# rx.net
KiCad netlist of a schematic drawn in EAGLE
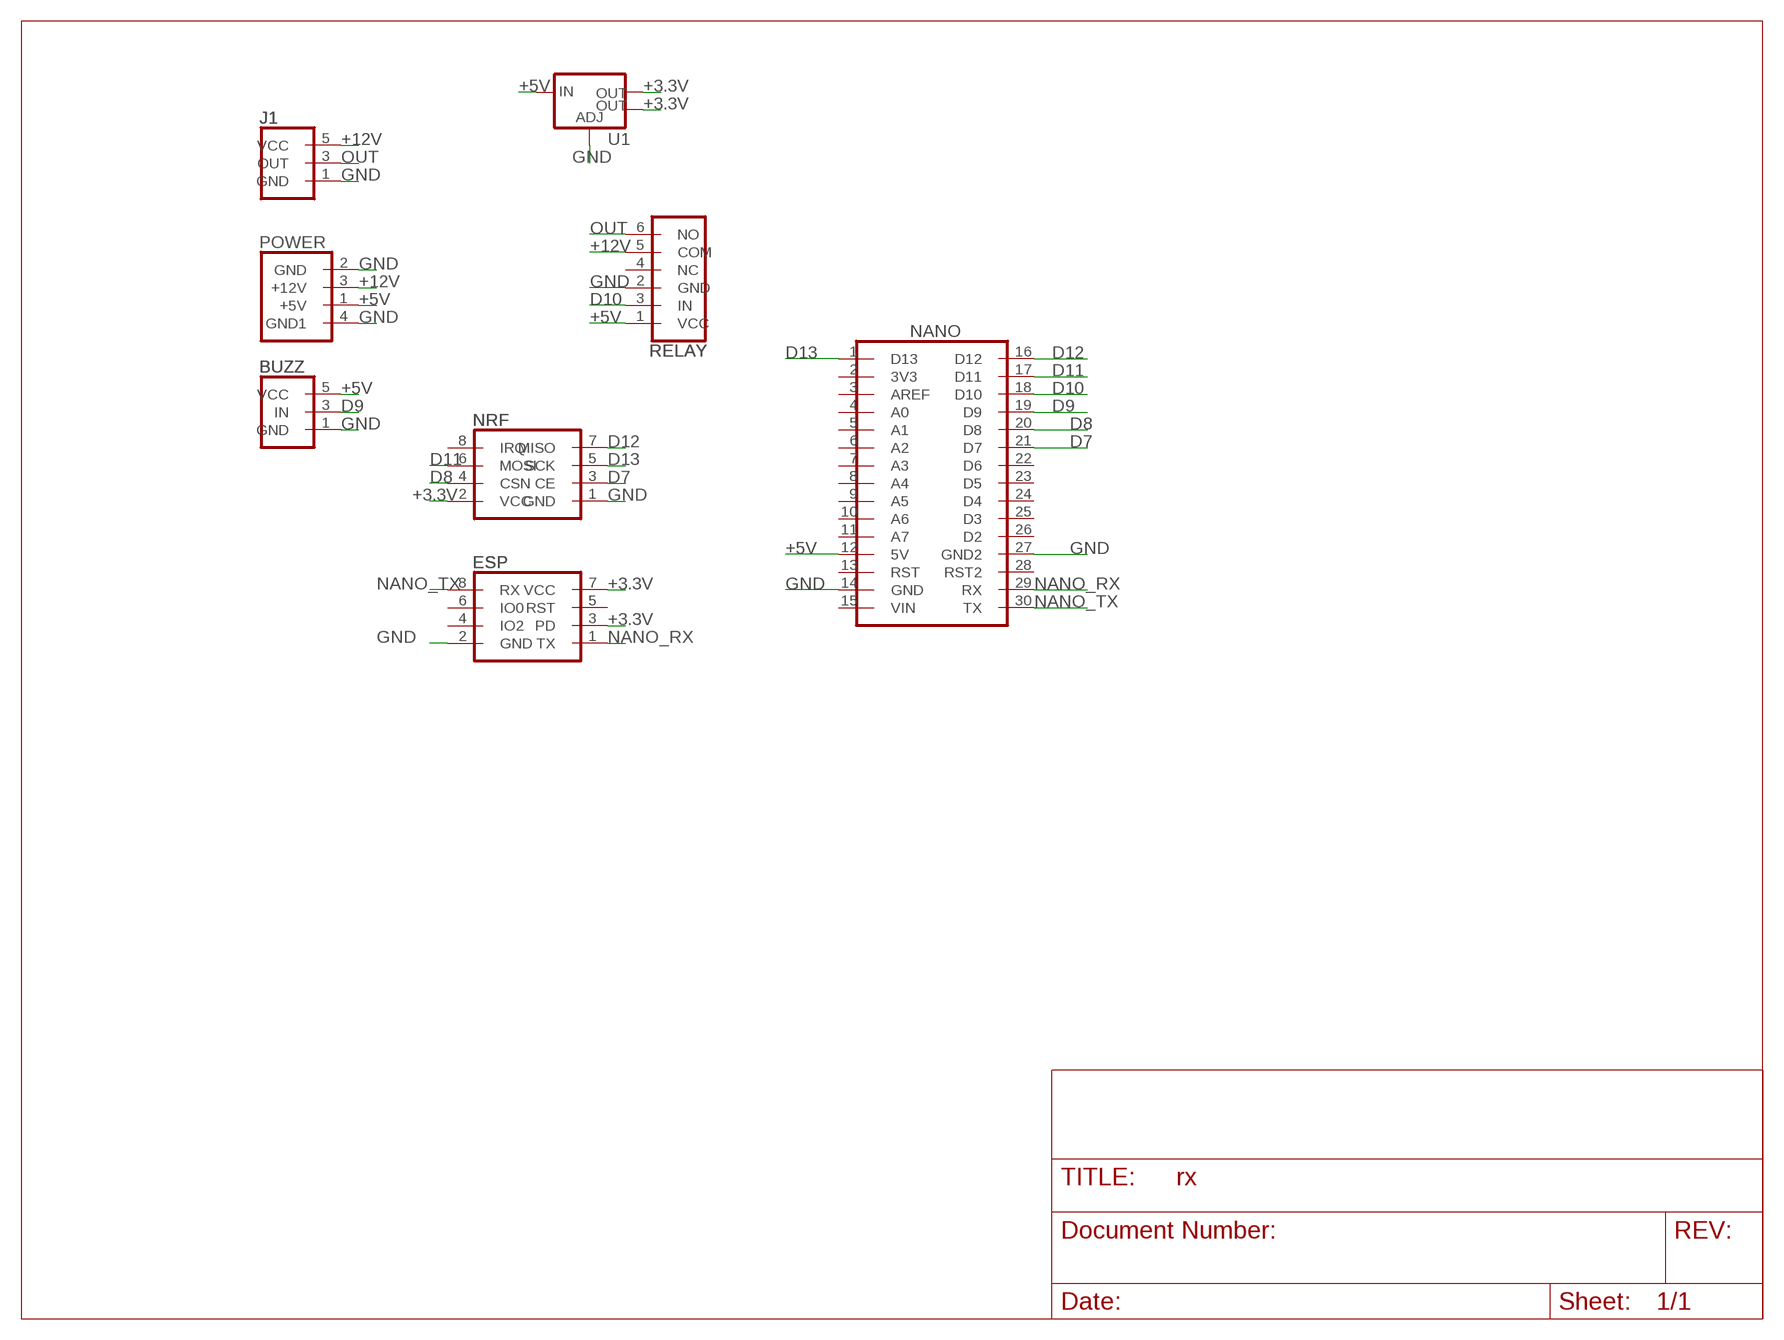
[diagram p0: schematic, sheet 1]

(export (version "E")
  (design (tool "Eeschema 10.0.6"))
  (components
    (comp (ref "BUZZ")
      (value "BUZZ_MODULE")
      (footprint "eagle-import:BUZZ_MODULE")
      (libsource (lib "eagle-import") (part "BUZZ_MODULE"))
    )
    (comp (ref "ESP")
      (value "ESP8266_MODULE")
      (footprint "eagle-import:ESP8266")
      (libsource (lib "eagle-import") (part "ESP8266_MODULE"))
    )
    (comp (ref "J1")
      (value "OUT_HEAD_3BIG")
      (footprint "eagle-import:OUT_HEAD_3_BIG")
      (libsource (lib "eagle-import") (part "OUT_HEAD_3BIG"))
    )
    (comp (ref "NANO")
      (value "ARDUINO_NANO")
      (footprint "eagle-import:ARDUINO_NANO")
      (libsource (lib "eagle-import") (part "ARDUINO_NANO"))
    )
    (comp (ref "NRF")
      (value "NRF24L01_MODULE_PA")
      (footprint "eagle-import:NRF24L01_PA")
      (libsource (lib "eagle-import") (part "NRF24L01_MODULE_PA"))
    )
    (comp (ref "POWER")
      (value "POWER_REDUCE")
      (footprint "eagle-import:POWER_REDUCE")
      (libsource (lib "eagle-import") (part "POWER_REDUCE"))
    )
    (comp (ref "RELAY")
      (value "RELAY_MODULE")
      (footprint "eagle-import:RELAY_MODULE")
      (libsource (lib "eagle-import") (part "RELAY_MODULE"))
    )
    (comp (ref "U1")
      (value "V_REG_LM1117SOT223")
      (footprint "eagle-import:SOT223")
      (libsource (lib "eagle-import") (part "V_REG_LM1117SOT223"))
    )
  )
  (nets
    (net (code "1") (name "/+3.3V") (class "Default")
      (node (ref "ESP") (pin "3") (pinfunction "PD_3") (pintype "bidirectional"))
      (node (ref "ESP") (pin "7") (pinfunction "VCC_7") (pintype "bidirectional"))
      (node (ref "NRF") (pin "2") (pinfunction "VCC_2") (pintype "bidirectional"))
      (node (ref "U1") (pin "2") (pinfunction "OUT_2") (pintype "output"))
      (node (ref "U1") (pin "4") (pinfunction "OUT_4") (pintype "output"))
    )
    (net (code "2") (name "/+5V") (class "Default")
      (node (ref "BUZZ") (pin "5") (pinfunction "VCC_5") (pintype "bidirectional"))
      (node (ref "NANO") (pin "12") (pinfunction "5V_12") (pintype "bidirectional"))
      (node (ref "POWER") (pin "1") (pinfunction "+5V_1") (pintype "bidirectional"))
      (node (ref "RELAY") (pin "1") (pinfunction "VCC_1") (pintype "bidirectional"))
      (node (ref "U1") (pin "3") (pinfunction "IN_3") (pintype "input"))
    )
    (net (code "3") (name "/+12V") (class "Default")
      (node (ref "J1") (pin "5") (pinfunction "VCC_5") (pintype "bidirectional"))
      (node (ref "POWER") (pin "3") (pinfunction "+12V_3") (pintype "bidirectional"))
      (node (ref "RELAY") (pin "5") (pinfunction "COM_5") (pintype "bidirectional"))
    )
    (net (code "4") (name "/D7") (class "Default")
      (node (ref "NANO") (pin "21") (pinfunction "D7_21") (pintype "bidirectional"))
      (node (ref "NRF") (pin "3") (pinfunction "CE_3") (pintype "bidirectional"))
    )
    (net (code "5") (name "/D8") (class "Default")
      (node (ref "NANO") (pin "20") (pinfunction "D8_20") (pintype "bidirectional"))
      (node (ref "NRF") (pin "4") (pinfunction "CSN_4") (pintype "bidirectional"))
    )
    (net (code "6") (name "/D9") (class "Default")
      (node (ref "BUZZ") (pin "3") (pinfunction "IN_3") (pintype "bidirectional"))
      (node (ref "NANO") (pin "19") (pinfunction "D9_19") (pintype "bidirectional"))
    )
    (net (code "7") (name "/D10") (class "Default")
      (node (ref "NANO") (pin "18") (pinfunction "D10_18") (pintype "bidirectional"))
      (node (ref "RELAY") (pin "3") (pinfunction "IN_3") (pintype "bidirectional"))
    )
    (net (code "8") (name "/D11") (class "Default")
      (node (ref "NANO") (pin "17") (pinfunction "D11_17") (pintype "bidirectional"))
      (node (ref "NRF") (pin "6") (pinfunction "MOSI_6") (pintype "bidirectional"))
    )
    (net (code "9") (name "/D12") (class "Default")
      (node (ref "NANO") (pin "16") (pinfunction "D12_16") (pintype "bidirectional"))
      (node (ref "NRF") (pin "7") (pinfunction "MISO_7") (pintype "bidirectional"))
    )
    (net (code "10") (name "/D13") (class "Default")
      (node (ref "NANO") (pin "1") (pinfunction "D13_1") (pintype "bidirectional"))
      (node (ref "NRF") (pin "5") (pinfunction "SCK_5") (pintype "bidirectional"))
    )
    (net (code "11") (name "/GND") (class "Default")
      (node (ref "BUZZ") (pin "1") (pinfunction "GND_1") (pintype "bidirectional"))
      (node (ref "ESP") (pin "2") (pinfunction "GND_2") (pintype "bidirectional"))
      (node (ref "J1") (pin "1") (pinfunction "GND_1") (pintype "bidirectional"))
      (node (ref "NANO") (pin "14") (pinfunction "GND_14") (pintype "bidirectional"))
      (node (ref "NANO") (pin "27") (pinfunction "GND2_27") (pintype "bidirectional"))
      (node (ref "NRF") (pin "1") (pinfunction "GND_1") (pintype "bidirectional"))
      (node (ref "POWER") (pin "2") (pinfunction "GND_2") (pintype "bidirectional"))
      (node (ref "POWER") (pin "4") (pinfunction "GND1_4") (pintype "bidirectional"))
      (node (ref "RELAY") (pin "2") (pinfunction "GND_2") (pintype "bidirectional"))
      (node (ref "U1") (pin "1") (pinfunction "ADJ_1") (pintype "input"))
    )
    (net (code "12") (name "/NANO_RX") (class "Default")
      (node (ref "ESP") (pin "1") (pinfunction "TX_1") (pintype "bidirectional"))
      (node (ref "NANO") (pin "29") (pinfunction "RX_29") (pintype "bidirectional"))
    )
    (net (code "13") (name "/NANO_TX") (class "Default")
      (node (ref "ESP") (pin "8") (pinfunction "RX_8") (pintype "bidirectional"))
      (node (ref "NANO") (pin "30") (pinfunction "TX_30") (pintype "bidirectional"))
    )
    (net (code "14") (name "/OUT") (class "Default")
      (node (ref "J1") (pin "3") (pinfunction "OUT_3") (pintype "bidirectional"))
      (node (ref "RELAY") (pin "6") (pinfunction "NO_6") (pintype "bidirectional"))
    )
    (net (code "15") (name "unconnected-(ESP-IO0-Pad6)") (class "Default")
      (node (ref "ESP") (pin "6") (pinfunction "IO0_6") (pintype "bidirectional"))
    )
    (net (code "16") (name "unconnected-(ESP-IO2-Pad4)") (class "Default")
      (node (ref "ESP") (pin "4") (pinfunction "IO2_4") (pintype "bidirectional"))
    )
    (net (code "17") (name "unconnected-(ESP-RST-Pad5)") (class "Default")
      (node (ref "ESP") (pin "5") (pinfunction "RST_5") (pintype "bidirectional"))
    )
    (net (code "18") (name "unconnected-(NANO-3V3-Pad2)") (class "Default")
      (node (ref "NANO") (pin "2") (pinfunction "3V3_2") (pintype "bidirectional"))
    )
    (net (code "19") (name "unconnected-(NANO-A0-Pad4)") (class "Default")
      (node (ref "NANO") (pin "4") (pinfunction "A0_4") (pintype "bidirectional"))
    )
    (net (code "20") (name "unconnected-(NANO-A1-Pad5)") (class "Default")
      (node (ref "NANO") (pin "5") (pinfunction "A1_5") (pintype "bidirectional"))
    )
    (net (code "21") (name "unconnected-(NANO-A2-Pad6)") (class "Default")
      (node (ref "NANO") (pin "6") (pinfunction "A2_6") (pintype "bidirectional"))
    )
    (net (code "22") (name "unconnected-(NANO-A3-Pad7)") (class "Default")
      (node (ref "NANO") (pin "7") (pinfunction "A3_7") (pintype "bidirectional"))
    )
    (net (code "23") (name "unconnected-(NANO-A4-Pad8)") (class "Default")
      (node (ref "NANO") (pin "8") (pinfunction "A4_8") (pintype "bidirectional"))
    )
    (net (code "24") (name "unconnected-(NANO-A5-Pad9)") (class "Default")
      (node (ref "NANO") (pin "9") (pinfunction "A5_9") (pintype "bidirectional"))
    )
    (net (code "25") (name "unconnected-(NANO-A6-Pad10)") (class "Default")
      (node (ref "NANO") (pin "10") (pinfunction "A6_10") (pintype "bidirectional"))
    )
    (net (code "26") (name "unconnected-(NANO-A7-Pad11)") (class "Default")
      (node (ref "NANO") (pin "11") (pinfunction "A7_11") (pintype "bidirectional"))
    )
    (net (code "27") (name "unconnected-(NANO-AREF-Pad3)") (class "Default")
      (node (ref "NANO") (pin "3") (pinfunction "AREF_3") (pintype "bidirectional"))
    )
    (net (code "28") (name "unconnected-(NANO-D2-Pad26)") (class "Default")
      (node (ref "NANO") (pin "26") (pinfunction "D2_26") (pintype "bidirectional"))
    )
    (net (code "29") (name "unconnected-(NANO-D3-Pad25)") (class "Default")
      (node (ref "NANO") (pin "25") (pinfunction "D3_25") (pintype "bidirectional"))
    )
    (net (code "30") (name "unconnected-(NANO-D4-Pad24)") (class "Default")
      (node (ref "NANO") (pin "24") (pinfunction "D4_24") (pintype "bidirectional"))
    )
    (net (code "31") (name "unconnected-(NANO-D5-Pad23)") (class "Default")
      (node (ref "NANO") (pin "23") (pinfunction "D5_23") (pintype "bidirectional"))
    )
    (net (code "32") (name "unconnected-(NANO-D6-Pad22)") (class "Default")
      (node (ref "NANO") (pin "22") (pinfunction "D6_22") (pintype "bidirectional"))
    )
    (net (code "33") (name "unconnected-(NANO-RST-Pad13)") (class "Default")
      (node (ref "NANO") (pin "13") (pinfunction "RST_13") (pintype "bidirectional"))
    )
    (net (code "34") (name "unconnected-(NANO-RST2-Pad28)") (class "Default")
      (node (ref "NANO") (pin "28") (pinfunction "RST2_28") (pintype "bidirectional"))
    )
    (net (code "35") (name "unconnected-(NANO-VIN-Pad15)") (class "Default")
      (node (ref "NANO") (pin "15") (pinfunction "VIN_15") (pintype "bidirectional"))
    )
    (net (code "36") (name "unconnected-(NRF-IRQ-Pad8)") (class "Default")
      (node (ref "NRF") (pin "8") (pinfunction "IRQ_8") (pintype "bidirectional"))
    )
    (net (code "37") (name "unconnected-(RELAY-NC-Pad4)") (class "Default")
      (node (ref "RELAY") (pin "4") (pinfunction "NC_4") (pintype "bidirectional"))
    )
  )
)
